# untitled.net
KiCad netlist of a schematic drawn in EAGLE
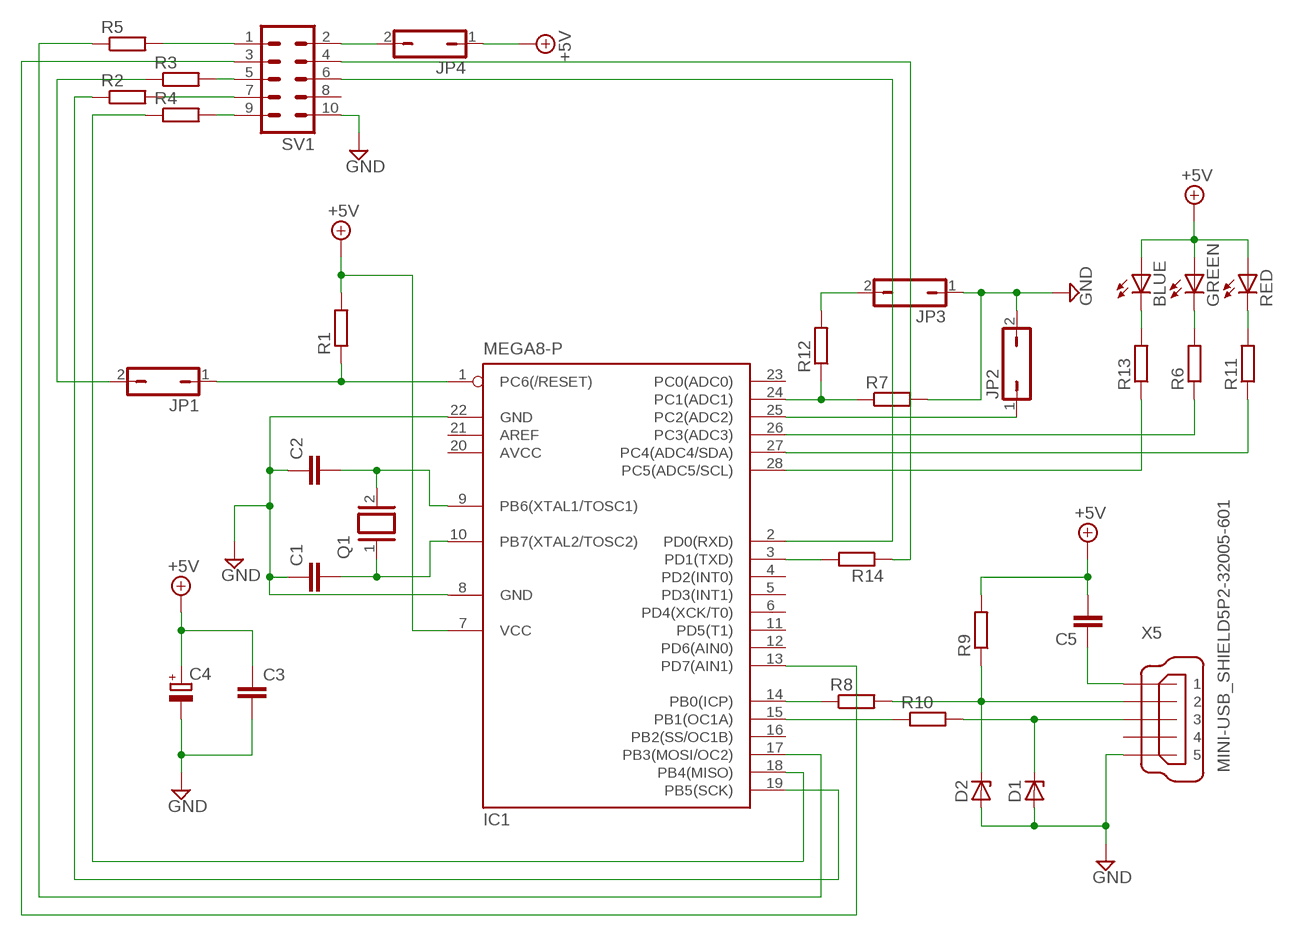
[diagram p0: schematic, sheet 1]

(export (version "E")
  (design (tool "Eeschema 10.0.6"))
  (components
    (comp (ref "BLUE")
      (value "LED5MM")
      (footprint "eagle-import:LED5MM")
      (libsource (lib "eagle-import") (part "LED5MM"))
    )
    (comp (ref "C1")
      (value "C-EU025-025X050")
      (footprint "eagle-import:C025-025X050")
      (libsource (lib "eagle-import") (part "C-EU025-025X050"))
    )
    (comp (ref "C2")
      (value "C-EU025-025X050")
      (footprint "eagle-import:C025-025X050")
      (libsource (lib "eagle-import") (part "C-EU025-025X050"))
    )
    (comp (ref "C3")
      (value "C-EU025_050-025X075")
      (footprint "eagle-import:C025_050-025X075")
      (libsource (lib "eagle-import") (part "C-EU025_050-025X075"))
    )
    (comp (ref "C4")
      (value "CPOL-EUE2.5-5")
      (footprint "eagle-import:E2,5-5")
      (libsource (lib "eagle-import") (part "CPOL-EUE2.5-5"))
    )
    (comp (ref "C5")
      (value "C-EU025_050-025X075")
      (footprint "eagle-import:C025_050-025X075")
      (libsource (lib "eagle-import") (part "C-EU025_050-025X075"))
    )
    (comp (ref "D1")
      (value "ZENER-DIODEZD-5")
      (footprint "eagle-import:ZDIO-5")
      (libsource (lib "eagle-import") (part "ZENER-DIODEZD-5"))
    )
    (comp (ref "D2")
      (value "ZENER-DIODEZD-2.5")
      (footprint "eagle-import:ZDIO-2.5")
      (libsource (lib "eagle-import") (part "ZENER-DIODEZD-2.5"))
    )
    (comp (ref "GREEN")
      (value "LED5MM")
      (footprint "eagle-import:LED5MM")
      (libsource (lib "eagle-import") (part "LED5MM"))
    )
    (comp (ref "IC1")
      (value "MEGA8-P")
      (footprint "eagle-import:DIL28-3")
      (libsource (lib "eagle-import") (part "MEGA8-P"))
    )
    (comp (ref "JP1")
      (value "JP1Q")
      (footprint "eagle-import:JP1")
      (libsource (lib "eagle-import") (part "JP1Q"))
    )
    (comp (ref "JP2")
      (value "JP1Q")
      (footprint "eagle-import:JP1")
      (libsource (lib "eagle-import") (part "JP1Q"))
    )
    (comp (ref "JP3")
      (value "JP1Q")
      (footprint "eagle-import:JP1")
      (libsource (lib "eagle-import") (part "JP1Q"))
    )
    (comp (ref "JP4")
      (value "JP1Q")
      (footprint "eagle-import:JP1")
      (libsource (lib "eagle-import") (part "JP1Q"))
    )
    (comp (ref "Q1")
      (value "XTAL/S")
      (footprint "eagle-import:QS")
      (libsource (lib "eagle-import") (part "XTAL/S"))
    )
    (comp (ref "R1")
      (value "R-EU_0207/2V")
      (footprint "eagle-import:0207_2V")
      (libsource (lib "eagle-import") (part "R-EU_0207/2V"))
    )
    (comp (ref "R2")
      (value "R-EU_0207/2V")
      (footprint "eagle-import:0207_2V")
      (libsource (lib "eagle-import") (part "R-EU_0207/2V"))
    )
    (comp (ref "R3")
      (value "R-EU_0207/2V")
      (footprint "eagle-import:0207_2V")
      (libsource (lib "eagle-import") (part "R-EU_0207/2V"))
    )
    (comp (ref "R4")
      (value "R-EU_0207/2V")
      (footprint "eagle-import:0207_2V")
      (libsource (lib "eagle-import") (part "R-EU_0207/2V"))
    )
    (comp (ref "R5")
      (value "R-EU_0207/2V")
      (footprint "eagle-import:0207_2V")
      (libsource (lib "eagle-import") (part "R-EU_0207/2V"))
    )
    (comp (ref "R6")
      (value "R-EU_0204/5")
      (footprint "eagle-import:0204_5")
      (libsource (lib "eagle-import") (part "R-EU_0204/5"))
    )
    (comp (ref "R7")
      (value "R-EU_0204/5")
      (footprint "eagle-import:0204_5")
      (libsource (lib "eagle-import") (part "R-EU_0204/5"))
    )
    (comp (ref "R8")
      (value "R-EU_0207/2V")
      (footprint "eagle-import:0207_2V")
      (libsource (lib "eagle-import") (part "R-EU_0207/2V"))
    )
    (comp (ref "R9")
      (value "R-EU_0207/2V")
      (footprint "eagle-import:0207_2V")
      (libsource (lib "eagle-import") (part "R-EU_0207/2V"))
    )
    (comp (ref "R10")
      (value "R-EU_0207/2V")
      (footprint "eagle-import:0207_2V")
      (libsource (lib "eagle-import") (part "R-EU_0207/2V"))
    )
    (comp (ref "R11")
      (value "R-EU_0204/5")
      (footprint "eagle-import:0204_5")
      (libsource (lib "eagle-import") (part "R-EU_0204/5"))
    )
    (comp (ref "R12")
      (value "R-EU_0204/5")
      (footprint "eagle-import:0204_5")
      (libsource (lib "eagle-import") (part "R-EU_0204/5"))
    )
    (comp (ref "R13")
      (value "R-EU_0204/5")
      (footprint "eagle-import:0204_5")
      (libsource (lib "eagle-import") (part "R-EU_0204/5"))
    )
    (comp (ref "R14")
      (value "R-EU_0207/2V")
      (footprint "eagle-import:0207_2V")
      (libsource (lib "eagle-import") (part "R-EU_0207/2V"))
    )
    (comp (ref "RED")
      (value "LED5MM")
      (footprint "eagle-import:LED5MM")
      (libsource (lib "eagle-import") (part "LED5MM"))
    )
    (comp (ref "SV1")
      (value "ML10")
      (footprint "eagle-import:ML10")
      (libsource (lib "eagle-import") (part "ML10"))
    )
    (comp (ref "X5")
      (value "MINI-USB_SHIELD5P2-32005-601")
      (footprint "eagle-import:32005-601")
      (libsource (lib "eagle-import") (part "MINI-USB_SHIELD5P2-32005-601"))
    )
  )
  (nets
    (net (code "1") (name "+5V") (class "Default")
      (node (ref "BLUE") (pin "A") (pinfunction "A_A") (pintype "passive"))
      (node (ref "C3") (pin "1") (pinfunction "1_1") (pintype "passive"))
      (node (ref "C4") (pin "+") (pinfunction "+_+") (pintype "passive"))
      (node (ref "C5") (pin "2") (pinfunction "2_2") (pintype "passive"))
      (node (ref "GREEN") (pin "A") (pinfunction "A_A") (pintype "passive"))
      (node (ref "IC1") (pin "7") (pinfunction "VCC_7") (pintype "power_in"))
      (node (ref "JP4") (pin "1") (pinfunction "1_1") (pintype "passive"))
      (node (ref "R1") (pin "2") (pinfunction "2_2") (pintype "passive"))
      (node (ref "R9") (pin "2") (pinfunction "2_2") (pintype "passive"))
      (node (ref "RED") (pin "A") (pinfunction "A_A") (pintype "passive"))
    )
    (net (code "2") (name "/AVCC") (class "Default")
      (node (ref "IC1") (pin "20") (pinfunction "AVCC_20") (pintype "power_in"))
    )
    (net (code "3") (name "GND") (class "Default")
      (node (ref "C1") (pin "1") (pinfunction "1_1") (pintype "passive"))
      (node (ref "C2") (pin "1") (pinfunction "1_1") (pintype "passive"))
      (node (ref "C3") (pin "2") (pinfunction "2_2") (pintype "passive"))
      (node (ref "C4") (pin "-") (pinfunction "-_-") (pintype "passive"))
      (node (ref "D1") (pin "A") (pinfunction "A_A") (pintype "passive"))
      (node (ref "D2") (pin "A") (pinfunction "A_A") (pintype "passive"))
      (node (ref "IC1") (pin "22") (pinfunction "GND_22") (pintype "power_in"))
      (node (ref "IC1") (pin "8") (pinfunction "GND_8") (pintype "power_in"))
      (node (ref "JP2") (pin "2") (pinfunction "2_2") (pintype "passive"))
      (node (ref "JP3") (pin "1") (pinfunction "1_1") (pintype "passive"))
      (node (ref "R7") (pin "2") (pinfunction "2_2") (pintype "passive"))
      (node (ref "SV1") (pin "10") (pinfunction "10_10") (pintype "passive"))
      (node (ref "X5") (pin "5") (pinfunction "5_5") (pintype "passive"))
    )
    (net (code "4") (name "Net-(BLUE-C)") (class "Default")
      (node (ref "BLUE") (pin "K") (pinfunction "C_K") (pintype "passive"))
      (node (ref "R13") (pin "2") (pinfunction "2_2") (pintype "passive"))
    )
    (net (code "5") (name "Net-(C5-Pad1)") (class "Default")
      (node (ref "C5") (pin "1") (pinfunction "1_1") (pintype "passive"))
      (node (ref "X5") (pin "1") (pinfunction "1_1") (pintype "passive"))
    )
    (net (code "6") (name "Net-(D1-PadC)") (class "Default")
      (node (ref "D1") (pin "C") (pinfunction "C_C") (pintype "passive"))
      (node (ref "R10") (pin "2") (pinfunction "2_2") (pintype "passive"))
      (node (ref "X5") (pin "3") (pinfunction "3_3") (pintype "passive"))
    )
    (net (code "7") (name "Net-(D2-PadC)") (class "Default")
      (node (ref "D2") (pin "C") (pinfunction "C_C") (pintype "passive"))
      (node (ref "R8") (pin "2") (pinfunction "2_2") (pintype "passive"))
      (node (ref "R9") (pin "1") (pinfunction "1_1") (pintype "passive"))
      (node (ref "X5") (pin "2") (pinfunction "2_2") (pintype "passive"))
    )
    (net (code "8") (name "Net-(GREEN-C)") (class "Default")
      (node (ref "GREEN") (pin "K") (pinfunction "C_K") (pintype "passive"))
      (node (ref "R6") (pin "2") (pinfunction "2_2") (pintype "passive"))
    )
    (net (code "9") (name "Net-(IC1-PB0(ICP))") (class "Default")
      (node (ref "IC1") (pin "14") (pinfunction "PB0(ICP)_14") (pintype "bidirectional"))
      (node (ref "R8") (pin "1") (pinfunction "1_1") (pintype "passive"))
    )
    (net (code "10") (name "Net-(IC1-PB1(OC1A))") (class "Default")
      (node (ref "IC1") (pin "15") (pinfunction "PB1(OC1A)_15") (pintype "bidirectional"))
      (node (ref "R10") (pin "1") (pinfunction "1_1") (pintype "passive"))
    )
    (net (code "11") (name "Net-(IC1-PB3(MOSI{slash}OC2))") (class "Default")
      (node (ref "IC1") (pin "17") (pinfunction "PB3(MOSI/OC2)_17") (pintype "bidirectional"))
      (node (ref "R5") (pin "1") (pinfunction "1_1") (pintype "passive"))
    )
    (net (code "12") (name "Net-(IC1-PB4(MISO))") (class "Default")
      (node (ref "IC1") (pin "18") (pinfunction "PB4(MISO)_18") (pintype "bidirectional"))
      (node (ref "R4") (pin "1") (pinfunction "1_1") (pintype "passive"))
    )
    (net (code "13") (name "Net-(IC1-PB5(SCK))") (class "Default")
      (node (ref "IC1") (pin "19") (pinfunction "PB5(SCK)_19") (pintype "bidirectional"))
      (node (ref "R2") (pin "1") (pinfunction "1_1") (pintype "passive"))
    )
    (net (code "14") (name "Net-(IC1-PB6(XTAL1{slash}TOSC1))") (class "Default")
      (node (ref "C2") (pin "2") (pinfunction "2_2") (pintype "passive"))
      (node (ref "IC1") (pin "9") (pinfunction "PB6(XTAL1/TOSC1)_9") (pintype "bidirectional"))
      (node (ref "Q1") (pin "2") (pinfunction "2_2") (pintype "passive"))
    )
    (net (code "15") (name "Net-(IC1-PB7(XTAL2{slash}TOSC2))") (class "Default")
      (node (ref "C1") (pin "2") (pinfunction "2_2") (pintype "passive"))
      (node (ref "IC1") (pin "10") (pinfunction "PB7(XTAL2/TOSC2)_10") (pintype "bidirectional"))
      (node (ref "Q1") (pin "1") (pinfunction "1_1") (pintype "passive"))
    )
    (net (code "16") (name "Net-(IC1-PC1(ADC1))") (class "Default")
      (node (ref "IC1") (pin "24") (pinfunction "PC1(ADC1)_24") (pintype "bidirectional"))
      (node (ref "R12") (pin "1") (pinfunction "1_1") (pintype "passive"))
      (node (ref "R7") (pin "1") (pinfunction "1_1") (pintype "passive"))
    )
    (net (code "17") (name "Net-(IC1-PC2(ADC2))") (class "Default")
      (node (ref "IC1") (pin "25") (pinfunction "PC2(ADC2)_25") (pintype "bidirectional"))
      (node (ref "JP2") (pin "1") (pinfunction "1_1") (pintype "passive"))
    )
    (net (code "18") (name "Net-(IC1-PC3(ADC3))") (class "Default")
      (node (ref "IC1") (pin "26") (pinfunction "PC3(ADC3)_26") (pintype "bidirectional"))
      (node (ref "R6") (pin "1") (pinfunction "1_1") (pintype "passive"))
    )
    (net (code "19") (name "Net-(IC1-PC4(ADC4{slash}SDA))") (class "Default")
      (node (ref "IC1") (pin "27") (pinfunction "PC4(ADC4/SDA)_27") (pintype "bidirectional"))
      (node (ref "R11") (pin "1") (pinfunction "1_1") (pintype "passive"))
    )
    (net (code "20") (name "Net-(IC1-PC5(ADC5{slash}SCL))") (class "Default")
      (node (ref "IC1") (pin "28") (pinfunction "PC5(ADC5/SCL)_28") (pintype "bidirectional"))
      (node (ref "R13") (pin "1") (pinfunction "1_1") (pintype "passive"))
    )
    (net (code "21") (name "Net-(IC1-PC6({slash}RESET))") (class "Default")
      (node (ref "IC1") (pin "1") (pinfunction "PC6(/RESET)_1") (pintype "bidirectional"))
      (node (ref "JP1") (pin "1") (pinfunction "1_1") (pintype "passive"))
      (node (ref "R1") (pin "1") (pinfunction "1_1") (pintype "passive"))
    )
    (net (code "22") (name "Net-(IC1-PD0(RXD))") (class "Default")
      (node (ref "IC1") (pin "2") (pinfunction "PD0(RXD)_2") (pintype "bidirectional"))
      (node (ref "SV1") (pin "6") (pinfunction "6_6") (pintype "passive"))
    )
    (net (code "23") (name "Net-(IC1-PD1(TXD))") (class "Default")
      (node (ref "IC1") (pin "3") (pinfunction "PD1(TXD)_3") (pintype "bidirectional"))
      (node (ref "R14") (pin "2") (pinfunction "2_2") (pintype "passive"))
    )
    (net (code "24") (name "Net-(IC1-PD7(AIN1))") (class "Default")
      (node (ref "IC1") (pin "13") (pinfunction "PD7(AIN1)_13") (pintype "bidirectional"))
      (node (ref "SV1") (pin "3") (pinfunction "3_3") (pintype "passive"))
    )
    (net (code "25") (name "Net-(JP1-Pad2)") (class "Default")
      (node (ref "JP1") (pin "2") (pinfunction "2_2") (pintype "passive"))
      (node (ref "R3") (pin "1") (pinfunction "1_1") (pintype "passive"))
    )
    (net (code "26") (name "Net-(JP3-Pad2)") (class "Default")
      (node (ref "JP3") (pin "2") (pinfunction "2_2") (pintype "passive"))
      (node (ref "R12") (pin "2") (pinfunction "2_2") (pintype "passive"))
    )
    (net (code "27") (name "Net-(JP4-Pad2)") (class "Default")
      (node (ref "JP4") (pin "2") (pinfunction "2_2") (pintype "passive"))
      (node (ref "SV1") (pin "2") (pinfunction "2_2") (pintype "passive"))
    )
    (net (code "28") (name "Net-(R2-Pad2)") (class "Default")
      (node (ref "R2") (pin "2") (pinfunction "2_2") (pintype "passive"))
      (node (ref "SV1") (pin "7") (pinfunction "7_7") (pintype "passive"))
    )
    (net (code "29") (name "Net-(R3-Pad2)") (class "Default")
      (node (ref "R3") (pin "2") (pinfunction "2_2") (pintype "passive"))
      (node (ref "SV1") (pin "5") (pinfunction "5_5") (pintype "passive"))
    )
    (net (code "30") (name "Net-(R4-Pad2)") (class "Default")
      (node (ref "R4") (pin "2") (pinfunction "2_2") (pintype "passive"))
      (node (ref "SV1") (pin "9") (pinfunction "9_9") (pintype "passive"))
    )
    (net (code "31") (name "Net-(R5-Pad2)") (class "Default")
      (node (ref "R5") (pin "2") (pinfunction "2_2") (pintype "passive"))
      (node (ref "SV1") (pin "1") (pinfunction "1_1") (pintype "passive"))
    )
    (net (code "32") (name "Net-(R14-Pad1)") (class "Default")
      (node (ref "R14") (pin "1") (pinfunction "1_1") (pintype "passive"))
      (node (ref "SV1") (pin "4") (pinfunction "4_4") (pintype "passive"))
    )
    (net (code "33") (name "Net-(RED-C)") (class "Default")
      (node (ref "R11") (pin "2") (pinfunction "2_2") (pintype "passive"))
      (node (ref "RED") (pin "K") (pinfunction "C_K") (pintype "passive"))
    )
    (net (code "34") (name "unconnected-(IC1-AREF-Pad21)") (class "Default")
      (node (ref "IC1") (pin "21") (pinfunction "AREF_21") (pintype "passive"))
    )
    (net (code "35") (name "unconnected-(IC1-PB2(SS{slash}OC1B)-Pad16)") (class "Default")
      (node (ref "IC1") (pin "16") (pinfunction "PB2(SS/OC1B)_16") (pintype "bidirectional"))
    )
    (net (code "36") (name "unconnected-(IC1-PC0(ADC0)-Pad23)") (class "Default")
      (node (ref "IC1") (pin "23") (pinfunction "PC0(ADC0)_23") (pintype "bidirectional"))
    )
    (net (code "37") (name "unconnected-(IC1-PD2(INT0)-Pad4)") (class "Default")
      (node (ref "IC1") (pin "4") (pinfunction "PD2(INT0)_4") (pintype "bidirectional"))
    )
    (net (code "38") (name "unconnected-(IC1-PD3(INT1)-Pad5)") (class "Default")
      (node (ref "IC1") (pin "5") (pinfunction "PD3(INT1)_5") (pintype "bidirectional"))
    )
    (net (code "39") (name "unconnected-(IC1-PD4(XCK{slash}T0)-Pad6)") (class "Default")
      (node (ref "IC1") (pin "6") (pinfunction "PD4(XCK/T0)_6") (pintype "bidirectional"))
    )
    (net (code "40") (name "unconnected-(IC1-PD5(T1)-Pad11)") (class "Default")
      (node (ref "IC1") (pin "11") (pinfunction "PD5(T1)_11") (pintype "bidirectional"))
    )
    (net (code "41") (name "unconnected-(IC1-PD6(AIN0)-Pad12)") (class "Default")
      (node (ref "IC1") (pin "12") (pinfunction "PD6(AIN0)_12") (pintype "bidirectional"))
    )
    (net (code "42") (name "unconnected-(SV1-Pad8)") (class "Default")
      (node (ref "SV1") (pin "8") (pinfunction "8_8") (pintype "passive"))
    )
    (net (code "43") (name "unconnected-(X5-Pad4)") (class "Default")
      (node (ref "X5") (pin "4") (pinfunction "4_4") (pintype "passive"))
    )
  )
)
